# PID_Controller.net
KiCad netlist of a schematic drawn in EAGLE
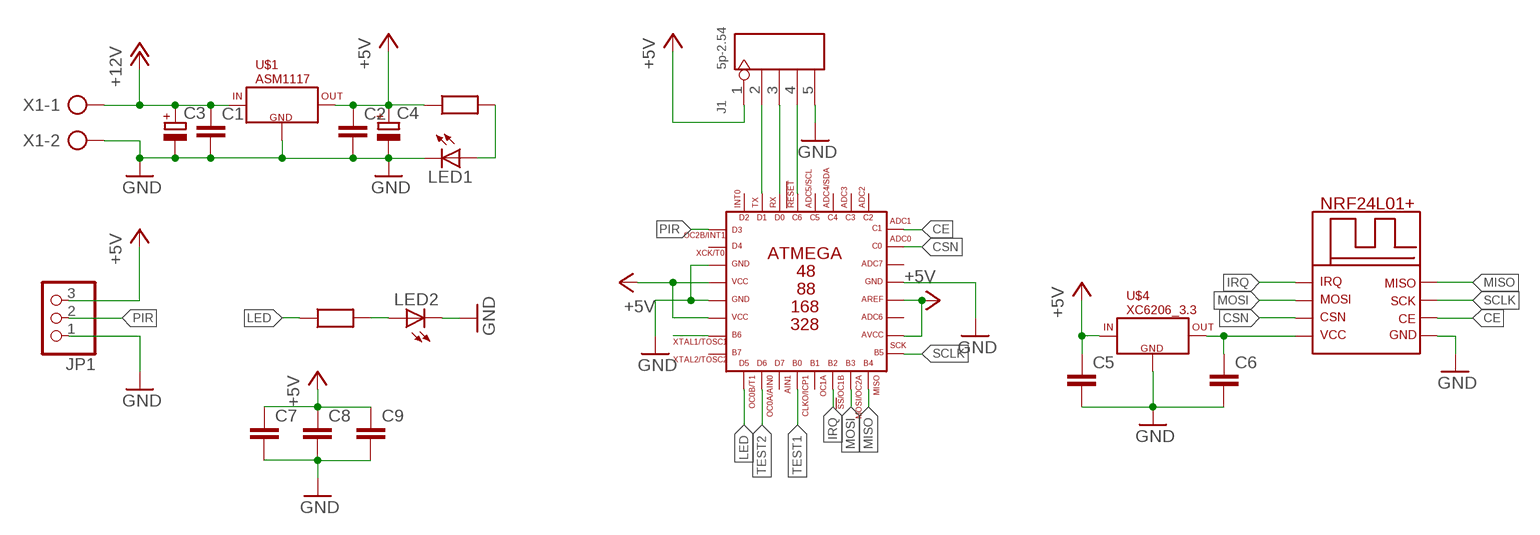
[diagram p0: schematic, sheet 1]

(export (version "E")
  (design (tool "Eeschema 10.0.6"))
  (components
    (comp (ref "C1")
      (value "C-EUC0805")
      (footprint "eagle-import:C0805")
      (libsource (lib "eagle-import") (part "C-EUC0805"))
    )
    (comp (ref "C2")
      (value "C-EUC0805")
      (footprint "eagle-import:C0805")
      (libsource (lib "eagle-import") (part "C-EUC0805"))
    )
    (comp (ref "C3")
      (value "CPOL-EUE2.5-6")
      (footprint "eagle-import:E2,5-6")
      (libsource (lib "eagle-import") (part "CPOL-EUE2.5-6"))
    )
    (comp (ref "C4")
      (value "CPOL-EUE2.5-6")
      (footprint "eagle-import:E2,5-6")
      (libsource (lib "eagle-import") (part "CPOL-EUE2.5-6"))
    )
    (comp (ref "C5")
      (value "C-EUC0805")
      (footprint "eagle-import:C0805")
      (libsource (lib "eagle-import") (part "C-EUC0805"))
    )
    (comp (ref "C6")
      (value "C-EUC0805")
      (footprint "eagle-import:C0805")
      (libsource (lib "eagle-import") (part "C-EUC0805"))
    )
    (comp (ref "C7")
      (value "C-EUC0805")
      (footprint "eagle-import:C0805")
      (libsource (lib "eagle-import") (part "C-EUC0805"))
    )
    (comp (ref "C8")
      (value "C-EUC0805")
      (footprint "eagle-import:C0805")
      (libsource (lib "eagle-import") (part "C-EUC0805"))
    )
    (comp (ref "C9")
      (value "C-EUC0805")
      (footprint "eagle-import:C0805")
      (libsource (lib "eagle-import") (part "C-EUC0805"))
    )
    (comp (ref "J1")
      (value "5p-2.54")
      (footprint "eagle-import:H5-2.54")
      (fields (field (name "MPN") "F185-1105A0BSYA1"))
      (libsource (lib "eagle-import") (part "DIP-BLACK-FEMALE-HEADER-VERT(5P-2.54)"))
    )
    (comp (ref "JP1")
      (value "PINHD-1X3")
      (footprint "eagle-import:1X03")
      (libsource (lib "eagle-import") (part "PINHD-1X3"))
    )
    (comp (ref "LED1")
      (value "LEDCHIP-LED0603")
      (footprint "eagle-import:CHIP-LED0603")
      (libsource (lib "eagle-import") (part "LEDCHIP-LED0603"))
    )
    (comp (ref "LED2")
      (value "LED3MM")
      (footprint "eagle-import:LED3MM")
      (libsource (lib "eagle-import") (part "LED3MM"))
    )
    (comp (ref "R1")
      (value "RES0603")
      (footprint "eagle-import:R0603")
      (libsource (lib "eagle-import") (part "RES0603"))
    )
    (comp (ref "R2")
      (value "RES0603")
      (footprint "eagle-import:R0603")
      (libsource (lib "eagle-import") (part "RES0603"))
    )
    (comp (ref "U$1")
      (value "ASM1117")
      (footprint "eagle-import:SOT223")
      (libsource (lib "eagle-import") (part "ASM1117"))
    )
    (comp (ref "U$2")
      (value "ATMEGAN8")
      (footprint "eagle-import:TQFP32-08")
      (libsource (lib "eagle-import") (part "ATMEGAN8"))
    )
    (comp (ref "U$3")
      (value "NRF24")
      (footprint "eagle-import:NRF")
      (libsource (lib "eagle-import") (part "NRF24"))
    )
    (comp (ref "U$4")
      (value "XC6206_3.3")
      (footprint "eagle-import:SOT23")
      (libsource (lib "eagle-import") (part "XC6206_3.3"))
    )
    (comp (ref "X1")
      (value "AK500/2")
      (footprint "eagle-import:AK500_2")
      (libsource (lib "eagle-import") (part "AK500/2"))
    )
  )
  (nets
    (net (code "1") (name "+5V") (class "Default")
      (node (ref "C2") (pin "1") (pinfunction "1_1") (pintype "passive"))
      (node (ref "C4") (pin "+") (pinfunction "+_+") (pintype "passive"))
      (node (ref "C5") (pin "1") (pinfunction "1_1") (pintype "passive"))
      (node (ref "C7") (pin "1") (pinfunction "1_1") (pintype "passive"))
      (node (ref "C8") (pin "1") (pinfunction "1_1") (pintype "passive"))
      (node (ref "C9") (pin "1") (pinfunction "1_1") (pintype "passive"))
      (node (ref "J1") (pin "1") (pinfunction "1_1") (pintype "bidirectional"))
      (node (ref "JP1") (pin "3") (pinfunction "3_3") (pintype "passive"))
      (node (ref "R1") (pin "1") (pinfunction "P$1_1") (pintype "bidirectional"))
      (node (ref "U$1") (pin "2") (pinfunction "OUT_2") (pintype "power_in"))
      (node (ref "U$1") (pin "4") (pinfunction "OUT_4") (pintype "power_in"))
      (node (ref "U$2") (pin "AREF") (pinfunction "AREF_AREF") (pintype "bidirectional"))
      (node (ref "U$2") (pin "AVCC") (pinfunction "AVCC_AVCC") (pintype "bidirectional"))
      (node (ref "U$2") (pin "VCC") (pinfunction "VCC_VCC") (pintype "bidirectional"))
      (node (ref "U$2") (pin "VCC1") (pinfunction "VCC1_VCC1") (pintype "bidirectional"))
      (node (ref "U$4") (pin "3") (pinfunction "IN_3") (pintype "power_in"))
    )
    (net (code "2") (name "+12V") (class "Default")
      (node (ref "C1") (pin "1") (pinfunction "1_1") (pintype "passive"))
      (node (ref "C3") (pin "+") (pinfunction "+_+") (pintype "passive"))
      (node (ref "U$1") (pin "3") (pinfunction "IN_3") (pintype "power_in"))
      (node (ref "X1") (pin "1") (pinfunction "KL_1") (pintype "passive"))
    )
    (net (code "3") (name "CE") (class "Default")
      (node (ref "U$2") (pin "C1") (pinfunction "C1_C1") (pintype "bidirectional"))
      (node (ref "U$3") (pin "CE") (pinfunction "CE_CE") (pintype "bidirectional"))
    )
    (net (code "4") (name "CSN") (class "Default")
      (node (ref "U$2") (pin "C0") (pinfunction "C0_C0") (pintype "bidirectional"))
      (node (ref "U$3") (pin "CSN") (pinfunction "CSN_CSN") (pintype "bidirectional"))
    )
    (net (code "5") (name "GND") (class "Default")
      (node (ref "C1") (pin "2") (pinfunction "2_2") (pintype "passive"))
      (node (ref "C2") (pin "2") (pinfunction "2_2") (pintype "passive"))
      (node (ref "C3") (pin "-") (pinfunction "-_-") (pintype "passive"))
      (node (ref "C4") (pin "-") (pinfunction "-_-") (pintype "passive"))
      (node (ref "C5") (pin "2") (pinfunction "2_2") (pintype "passive"))
      (node (ref "C6") (pin "2") (pinfunction "2_2") (pintype "passive"))
      (node (ref "C7") (pin "2") (pinfunction "2_2") (pintype "passive"))
      (node (ref "C8") (pin "2") (pinfunction "2_2") (pintype "passive"))
      (node (ref "C9") (pin "2") (pinfunction "2_2") (pintype "passive"))
      (node (ref "J1") (pin "5") (pinfunction "5_5") (pintype "bidirectional"))
      (node (ref "JP1") (pin "1") (pinfunction "1_1") (pintype "passive"))
      (node (ref "LED1") (pin "C") (pinfunction "C_C") (pintype "passive"))
      (node (ref "LED2") (pin "K") (pinfunction "C_K") (pintype "passive"))
      (node (ref "U$1") (pin "1") (pinfunction "GND_1") (pintype "power_in"))
      (node (ref "U$2") (pin "GND") (pinfunction "GND_GND") (pintype "bidirectional"))
      (node (ref "U$2") (pin "GND1") (pinfunction "GND1_GND1") (pintype "bidirectional"))
      (node (ref "U$2") (pin "GND2") (pinfunction "GND2_GND2") (pintype "bidirectional"))
      (node (ref "U$3") (pin "GND") (pinfunction "GND_GND") (pintype "bidirectional"))
      (node (ref "U$4") (pin "1") (pinfunction "GND_1") (pintype "power_in"))
      (node (ref "X1") (pin "2") (pinfunction "KL_2") (pintype "passive"))
    )
    (net (code "6") (name "IRQ") (class "Default")
      (node (ref "U$2") (pin "B2") (pinfunction "B2_B2") (pintype "bidirectional"))
      (node (ref "U$3") (pin "IRQ") (pinfunction "IRQ_IRQ") (pintype "bidirectional"))
    )
    (net (code "7") (name "LED") (class "Default")
      (node (ref "R2") (pin "1") (pinfunction "P$1_1") (pintype "bidirectional"))
      (node (ref "U$2") (pin "D5") (pinfunction "D5_D5") (pintype "bidirectional"))
    )
    (net (code "8") (name "MISO") (class "Default")
      (node (ref "U$2") (pin "B4") (pinfunction "B4_B4") (pintype "bidirectional"))
      (node (ref "U$3") (pin "MISO") (pinfunction "MISO_MISO") (pintype "bidirectional"))
    )
    (net (code "9") (name "MOSI") (class "Default")
      (node (ref "U$2") (pin "B3") (pinfunction "B3_B3") (pintype "bidirectional"))
      (node (ref "U$3") (pin "MOSI") (pinfunction "MOSI_MOSI") (pintype "bidirectional"))
    )
    (net (code "10") (name "Net-(J1-Pad2)") (class "Default")
      (node (ref "J1") (pin "2") (pinfunction "2_2") (pintype "bidirectional"))
      (node (ref "U$2") (pin "D1") (pinfunction "D1_D1") (pintype "bidirectional"))
    )
    (net (code "11") (name "Net-(J1-Pad3)") (class "Default")
      (node (ref "J1") (pin "3") (pinfunction "3_3") (pintype "bidirectional"))
      (node (ref "U$2") (pin "D0") (pinfunction "D0_D0") (pintype "bidirectional"))
    )
    (net (code "12") (name "Net-(J1-Pad4)") (class "Default")
      (node (ref "J1") (pin "4") (pinfunction "4_4") (pintype "bidirectional"))
      (node (ref "U$2") (pin "C6") (pinfunction "C6_C6") (pintype "bidirectional"))
    )
    (net (code "13") (name "Net-(R1-P$2)") (class "Default")
      (node (ref "LED1") (pin "A") (pinfunction "A_A") (pintype "passive"))
      (node (ref "R1") (pin "2") (pinfunction "P$2_2") (pintype "bidirectional"))
    )
    (net (code "14") (name "Net-(R2-P$2)") (class "Default")
      (node (ref "LED2") (pin "A") (pinfunction "A_A") (pintype "passive"))
      (node (ref "R2") (pin "2") (pinfunction "P$2_2") (pintype "bidirectional"))
    )
    (net (code "15") (name "Net-(U$4-OUT)") (class "Default")
      (node (ref "C6") (pin "1") (pinfunction "1_1") (pintype "passive"))
      (node (ref "U$3") (pin "VCC") (pinfunction "VCC_VCC") (pintype "bidirectional"))
      (node (ref "U$4") (pin "2") (pinfunction "OUT_2") (pintype "power_in"))
    )
    (net (code "16") (name "PIR") (class "Default")
      (node (ref "JP1") (pin "2") (pinfunction "2_2") (pintype "passive"))
      (node (ref "U$2") (pin "D3") (pinfunction "D3_D3") (pintype "bidirectional"))
    )
    (net (code "17") (name "SCLK") (class "Default")
      (node (ref "U$2") (pin "B5") (pinfunction "B5_B5") (pintype "bidirectional"))
      (node (ref "U$3") (pin "SCK") (pinfunction "SCK_SCK") (pintype "bidirectional"))
    )
    (net (code "18") (name "TEST1") (class "Default")
      (node (ref "U$2") (pin "B0") (pinfunction "B0_B0") (pintype "bidirectional"))
    )
    (net (code "19") (name "TEST2") (class "Default")
      (node (ref "U$2") (pin "D6") (pinfunction "D6_D6") (pintype "bidirectional"))
    )
    (net (code "20") (name "unconnected-(U$2-PadADC6)") (class "Default")
      (node (ref "U$2") (pin "ADC6") (pinfunction "ADC6_ADC6") (pintype "bidirectional"))
    )
    (net (code "21") (name "unconnected-(U$2-PadADC7)") (class "Default")
      (node (ref "U$2") (pin "ADC7") (pinfunction "ADC7_ADC7") (pintype "bidirectional"))
    )
    (net (code "22") (name "unconnected-(U$2-PadB1)") (class "Default")
      (node (ref "U$2") (pin "B1") (pinfunction "B1_B1") (pintype "bidirectional"))
    )
    (net (code "23") (name "unconnected-(U$2-PadB6)") (class "Default")
      (node (ref "U$2") (pin "B6") (pinfunction "B6_B6") (pintype "bidirectional"))
    )
    (net (code "24") (name "unconnected-(U$2-PadB7)") (class "Default")
      (node (ref "U$2") (pin "B7") (pinfunction "B7_B7") (pintype "bidirectional"))
    )
    (net (code "25") (name "unconnected-(U$2-PadC2)") (class "Default")
      (node (ref "U$2") (pin "C2") (pinfunction "C2_C2") (pintype "bidirectional"))
    )
    (net (code "26") (name "unconnected-(U$2-PadC3)") (class "Default")
      (node (ref "U$2") (pin "C3") (pinfunction "C3_C3") (pintype "bidirectional"))
    )
    (net (code "27") (name "unconnected-(U$2-PadC4)") (class "Default")
      (node (ref "U$2") (pin "C4") (pinfunction "C4_C4") (pintype "bidirectional"))
    )
    (net (code "28") (name "unconnected-(U$2-PadC5)") (class "Default")
      (node (ref "U$2") (pin "C5") (pinfunction "C5_C5") (pintype "bidirectional"))
    )
    (net (code "29") (name "unconnected-(U$2-PadD2)") (class "Default")
      (node (ref "U$2") (pin "D2") (pinfunction "D2_D2") (pintype "bidirectional"))
    )
    (net (code "30") (name "unconnected-(U$2-PadD4)") (class "Default")
      (node (ref "U$2") (pin "D4") (pinfunction "D4_D4") (pintype "bidirectional"))
    )
    (net (code "31") (name "unconnected-(U$2-PadD7)") (class "Default")
      (node (ref "U$2") (pin "D7") (pinfunction "D7_D7") (pintype "bidirectional"))
    )
  )
)
